# io.net
KiCad netlist of a schematic drawn in Altium Designer
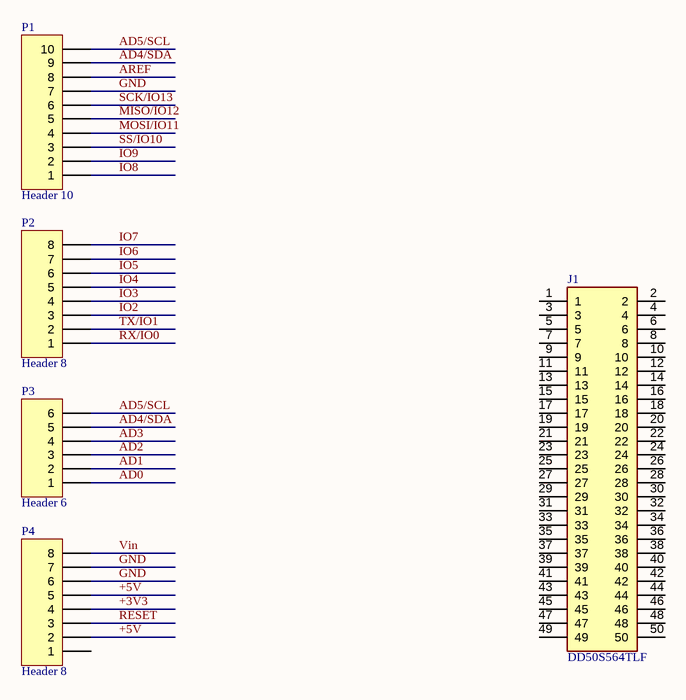
[diagram p0: io.SchDoc]

(export (version "E")
  (design (tool "Eeschema 10.0.6"))
  (components
    (comp (ref "J1")
      (value "DD50S564TLF")
      (footprint "SamacSys:DD50S564TLF")
      (description "Connector")
      (fields (field (name "MOUSER PART NUMBER") "649-DD50S564TLF") (field (name "RS PART NUMBER") "1217375"))
      (libsource (lib "*") (part "DD50S564TLF"))
    )
    (comp (ref "P1")
      (value "Header 10")
      (footprint "HDR1X10")
      (description "Header, 10-Pin")
      (fields (field (name "PUBLISHER") "Altium Limited"))
      (libsource (lib "Miscellaneous Connectors") (part "Header 10"))
    )
    (comp (ref "P2")
      (value "Header 8")
      (footprint "HDR1X8")
      (description "Header, 8-Pin")
      (fields (field (name "PUBLISHER") "Altium Limited"))
      (libsource (lib "Miscellaneous Connectors") (part "Header 8"))
    )
    (comp (ref "P3")
      (value "Header 6")
      (footprint "HDR1X6")
      (description "Header, 6-Pin")
      (fields (field (name "PUBLISHER") "Altium Limited"))
      (libsource (lib "Miscellaneous Connectors") (part "Header 6"))
    )
    (comp (ref "P4")
      (value "Header 8")
      (footprint "HDR1X8")
      (description "Header, 8-Pin")
      (fields (field (name "PUBLISHER") "Altium Limited"))
      (libsource (lib "Miscellaneous Connectors") (part "Header 8"))
    )
  )
  (nets
    (net (code "1") (name "/+3V3") (class "Default")
      (node (ref "P4") (pin "4") (pinfunction "4_4") (pintype "passive"))
    )
    (net (code "2") (name "/+5V") (class "Default")
      (node (ref "P4") (pin "2") (pinfunction "2_2") (pintype "passive"))
      (node (ref "P4") (pin "5") (pinfunction "5_5") (pintype "passive"))
    )
    (net (code "3") (name "/AD0") (class "Default")
      (node (ref "P3") (pin "1") (pinfunction "1_1") (pintype "passive"))
    )
    (net (code "4") (name "/AD1") (class "Default")
      (node (ref "P3") (pin "2") (pinfunction "2_2") (pintype "passive"))
    )
    (net (code "5") (name "/AD2") (class "Default")
      (node (ref "P3") (pin "3") (pinfunction "3_3") (pintype "passive"))
    )
    (net (code "6") (name "/AD3") (class "Default")
      (node (ref "P3") (pin "4") (pinfunction "4_4") (pintype "passive"))
    )
    (net (code "7") (name "/AD4{slash}SDA") (class "Default")
      (node (ref "P1") (pin "9") (pinfunction "9_9") (pintype "passive"))
      (node (ref "P3") (pin "5") (pinfunction "5_5") (pintype "passive"))
    )
    (net (code "8") (name "/AD5{slash}SCL") (class "Default")
      (node (ref "P1") (pin "10") (pinfunction "10_10") (pintype "passive"))
      (node (ref "P3") (pin "6") (pinfunction "6_6") (pintype "passive"))
    )
    (net (code "9") (name "/AREF") (class "Default")
      (node (ref "P1") (pin "8") (pinfunction "8_8") (pintype "passive"))
    )
    (net (code "10") (name "/GND") (class "Default")
      (node (ref "P1") (pin "7") (pinfunction "7_7") (pintype "passive"))
      (node (ref "P4") (pin "6") (pinfunction "6_6") (pintype "passive"))
      (node (ref "P4") (pin "7") (pinfunction "7_7") (pintype "passive"))
    )
    (net (code "11") (name "/IO2") (class "Default")
      (node (ref "P2") (pin "3") (pinfunction "3_3") (pintype "passive"))
    )
    (net (code "12") (name "/IO3") (class "Default")
      (node (ref "P2") (pin "4") (pinfunction "4_4") (pintype "passive"))
    )
    (net (code "13") (name "/IO4") (class "Default")
      (node (ref "P2") (pin "5") (pinfunction "5_5") (pintype "passive"))
    )
    (net (code "14") (name "/IO5") (class "Default")
      (node (ref "P2") (pin "6") (pinfunction "6_6") (pintype "passive"))
    )
    (net (code "15") (name "/IO6") (class "Default")
      (node (ref "P2") (pin "7") (pinfunction "7_7") (pintype "passive"))
    )
    (net (code "16") (name "/IO7") (class "Default")
      (node (ref "P2") (pin "8") (pinfunction "8_8") (pintype "passive"))
    )
    (net (code "17") (name "/IO8") (class "Default")
      (node (ref "P1") (pin "1") (pinfunction "1_1") (pintype "passive"))
    )
    (net (code "18") (name "/IO9") (class "Default")
      (node (ref "P1") (pin "2") (pinfunction "2_2") (pintype "passive"))
    )
    (net (code "19") (name "/MISO{slash}IO12") (class "Default")
      (node (ref "P1") (pin "5") (pinfunction "5_5") (pintype "passive"))
    )
    (net (code "20") (name "/MOSI{slash}IO11") (class "Default")
      (node (ref "P1") (pin "4") (pinfunction "4_4") (pintype "passive"))
    )
    (net (code "21") (name "/RESET") (class "Default")
      (node (ref "P4") (pin "3") (pinfunction "3_3") (pintype "passive"))
    )
    (net (code "22") (name "/RX{slash}IO0") (class "Default")
      (node (ref "P2") (pin "1") (pinfunction "1_1") (pintype "passive"))
    )
    (net (code "23") (name "/SCK{slash}IO13") (class "Default")
      (node (ref "P1") (pin "6") (pinfunction "6_6") (pintype "passive"))
    )
    (net (code "24") (name "/SS{slash}IO10") (class "Default")
      (node (ref "P1") (pin "3") (pinfunction "3_3") (pintype "passive"))
    )
    (net (code "25") (name "/TX{slash}IO1") (class "Default")
      (node (ref "P2") (pin "2") (pinfunction "2_2") (pintype "passive"))
    )
    (net (code "26") (name "/Vin") (class "Default")
      (node (ref "P4") (pin "8") (pinfunction "8_8") (pintype "passive"))
    )
    (net (code "27") (name "unconnected-(J1-Pad1)") (class "Default")
      (node (ref "J1") (pin "1") (pinfunction "1_1") (pintype "passive"))
    )
    (net (code "28") (name "unconnected-(J1-Pad2)") (class "Default")
      (node (ref "J1") (pin "2") (pinfunction "2_2") (pintype "passive"))
    )
    (net (code "29") (name "unconnected-(J1-Pad3)") (class "Default")
      (node (ref "J1") (pin "3") (pinfunction "3_3") (pintype "passive"))
    )
    (net (code "30") (name "unconnected-(J1-Pad4)") (class "Default")
      (node (ref "J1") (pin "4") (pinfunction "4_4") (pintype "passive"))
    )
    (net (code "31") (name "unconnected-(J1-Pad5)") (class "Default")
      (node (ref "J1") (pin "5") (pinfunction "5_5") (pintype "passive"))
    )
    (net (code "32") (name "unconnected-(J1-Pad6)") (class "Default")
      (node (ref "J1") (pin "6") (pinfunction "6_6") (pintype "passive"))
    )
    (net (code "33") (name "unconnected-(J1-Pad7)") (class "Default")
      (node (ref "J1") (pin "7") (pinfunction "7_7") (pintype "passive"))
    )
    (net (code "34") (name "unconnected-(J1-Pad8)") (class "Default")
      (node (ref "J1") (pin "8") (pinfunction "8_8") (pintype "passive"))
    )
    (net (code "35") (name "unconnected-(J1-Pad9)") (class "Default")
      (node (ref "J1") (pin "9") (pinfunction "9_9") (pintype "passive"))
    )
    (net (code "36") (name "unconnected-(J1-Pad10)") (class "Default")
      (node (ref "J1") (pin "10") (pinfunction "10_10") (pintype "passive"))
    )
    (net (code "37") (name "unconnected-(J1-Pad11)") (class "Default")
      (node (ref "J1") (pin "11") (pinfunction "11_11") (pintype "passive"))
    )
    (net (code "38") (name "unconnected-(J1-Pad12)") (class "Default")
      (node (ref "J1") (pin "12") (pinfunction "12_12") (pintype "passive"))
    )
    (net (code "39") (name "unconnected-(J1-Pad13)") (class "Default")
      (node (ref "J1") (pin "13") (pinfunction "13_13") (pintype "passive"))
    )
    (net (code "40") (name "unconnected-(J1-Pad14)") (class "Default")
      (node (ref "J1") (pin "14") (pinfunction "14_14") (pintype "passive"))
    )
    (net (code "41") (name "unconnected-(J1-Pad15)") (class "Default")
      (node (ref "J1") (pin "15") (pinfunction "15_15") (pintype "passive"))
    )
    (net (code "42") (name "unconnected-(J1-Pad16)") (class "Default")
      (node (ref "J1") (pin "16") (pinfunction "16_16") (pintype "passive"))
    )
    (net (code "43") (name "unconnected-(J1-Pad17)") (class "Default")
      (node (ref "J1") (pin "17") (pinfunction "17_17") (pintype "passive"))
    )
    (net (code "44") (name "unconnected-(J1-Pad18)") (class "Default")
      (node (ref "J1") (pin "18") (pinfunction "18_18") (pintype "passive"))
    )
    (net (code "45") (name "unconnected-(J1-Pad19)") (class "Default")
      (node (ref "J1") (pin "19") (pinfunction "19_19") (pintype "passive"))
    )
    (net (code "46") (name "unconnected-(J1-Pad20)") (class "Default")
      (node (ref "J1") (pin "20") (pinfunction "20_20") (pintype "passive"))
    )
    (net (code "47") (name "unconnected-(J1-Pad21)") (class "Default")
      (node (ref "J1") (pin "21") (pinfunction "21_21") (pintype "passive"))
    )
    (net (code "48") (name "unconnected-(J1-Pad22)") (class "Default")
      (node (ref "J1") (pin "22") (pinfunction "22_22") (pintype "passive"))
    )
    (net (code "49") (name "unconnected-(J1-Pad23)") (class "Default")
      (node (ref "J1") (pin "23") (pinfunction "23_23") (pintype "passive"))
    )
    (net (code "50") (name "unconnected-(J1-Pad24)") (class "Default")
      (node (ref "J1") (pin "24") (pinfunction "24_24") (pintype "passive"))
    )
    (net (code "51") (name "unconnected-(J1-Pad25)") (class "Default")
      (node (ref "J1") (pin "25") (pinfunction "25_25") (pintype "passive"))
    )
    (net (code "52") (name "unconnected-(J1-Pad26)") (class "Default")
      (node (ref "J1") (pin "26") (pinfunction "26_26") (pintype "passive"))
    )
    (net (code "53") (name "unconnected-(J1-Pad27)") (class "Default")
      (node (ref "J1") (pin "27") (pinfunction "27_27") (pintype "passive"))
    )
    (net (code "54") (name "unconnected-(J1-Pad28)") (class "Default")
      (node (ref "J1") (pin "28") (pinfunction "28_28") (pintype "passive"))
    )
    (net (code "55") (name "unconnected-(J1-Pad29)") (class "Default")
      (node (ref "J1") (pin "29") (pinfunction "29_29") (pintype "passive"))
    )
    (net (code "56") (name "unconnected-(J1-Pad30)") (class "Default")
      (node (ref "J1") (pin "30") (pinfunction "30_30") (pintype "passive"))
    )
    (net (code "57") (name "unconnected-(J1-Pad31)") (class "Default")
      (node (ref "J1") (pin "31") (pinfunction "31_31") (pintype "passive"))
    )
    (net (code "58") (name "unconnected-(J1-Pad32)") (class "Default")
      (node (ref "J1") (pin "32") (pinfunction "32_32") (pintype "passive"))
    )
    (net (code "59") (name "unconnected-(J1-Pad33)") (class "Default")
      (node (ref "J1") (pin "33") (pinfunction "33_33") (pintype "passive"))
    )
    (net (code "60") (name "unconnected-(J1-Pad34)") (class "Default")
      (node (ref "J1") (pin "34") (pinfunction "34_34") (pintype "passive"))
    )
    (net (code "61") (name "unconnected-(J1-Pad35)") (class "Default")
      (node (ref "J1") (pin "35") (pinfunction "35_35") (pintype "passive"))
    )
    (net (code "62") (name "unconnected-(J1-Pad36)") (class "Default")
      (node (ref "J1") (pin "36") (pinfunction "36_36") (pintype "passive"))
    )
    (net (code "63") (name "unconnected-(J1-Pad37)") (class "Default")
      (node (ref "J1") (pin "37") (pinfunction "37_37") (pintype "passive"))
    )
    (net (code "64") (name "unconnected-(J1-Pad38)") (class "Default")
      (node (ref "J1") (pin "38") (pinfunction "38_38") (pintype "passive"))
    )
    (net (code "65") (name "unconnected-(J1-Pad39)") (class "Default")
      (node (ref "J1") (pin "39") (pinfunction "39_39") (pintype "passive"))
    )
    (net (code "66") (name "unconnected-(J1-Pad40)") (class "Default")
      (node (ref "J1") (pin "40") (pinfunction "40_40") (pintype "passive"))
    )
    (net (code "67") (name "unconnected-(J1-Pad41)") (class "Default")
      (node (ref "J1") (pin "41") (pinfunction "41_41") (pintype "passive"))
    )
    (net (code "68") (name "unconnected-(J1-Pad42)") (class "Default")
      (node (ref "J1") (pin "42") (pinfunction "42_42") (pintype "passive"))
    )
    (net (code "69") (name "unconnected-(J1-Pad43)") (class "Default")
      (node (ref "J1") (pin "43") (pinfunction "43_43") (pintype "passive"))
    )
    (net (code "70") (name "unconnected-(J1-Pad44)") (class "Default")
      (node (ref "J1") (pin "44") (pinfunction "44_44") (pintype "passive"))
    )
    (net (code "71") (name "unconnected-(J1-Pad45)") (class "Default")
      (node (ref "J1") (pin "45") (pinfunction "45_45") (pintype "passive"))
    )
    (net (code "72") (name "unconnected-(J1-Pad46)") (class "Default")
      (node (ref "J1") (pin "46") (pinfunction "46_46") (pintype "passive"))
    )
    (net (code "73") (name "unconnected-(J1-Pad47)") (class "Default")
      (node (ref "J1") (pin "47") (pinfunction "47_47") (pintype "passive"))
    )
    (net (code "74") (name "unconnected-(J1-Pad48)") (class "Default")
      (node (ref "J1") (pin "48") (pinfunction "48_48") (pintype "passive"))
    )
    (net (code "75") (name "unconnected-(J1-Pad49)") (class "Default")
      (node (ref "J1") (pin "49") (pinfunction "49_49") (pintype "passive"))
    )
    (net (code "76") (name "unconnected-(J1-Pad50)") (class "Default")
      (node (ref "J1") (pin "50") (pinfunction "50_50") (pintype "passive"))
    )
    (net (code "77") (name "unconnected-(P4-Pad1)") (class "Default")
      (node (ref "P4") (pin "1") (pinfunction "1_1") (pintype "passive"))
    )
  )
)
